# RM-KM-CS.net
KiCad netlist of a schematic drawn in Altium Designer
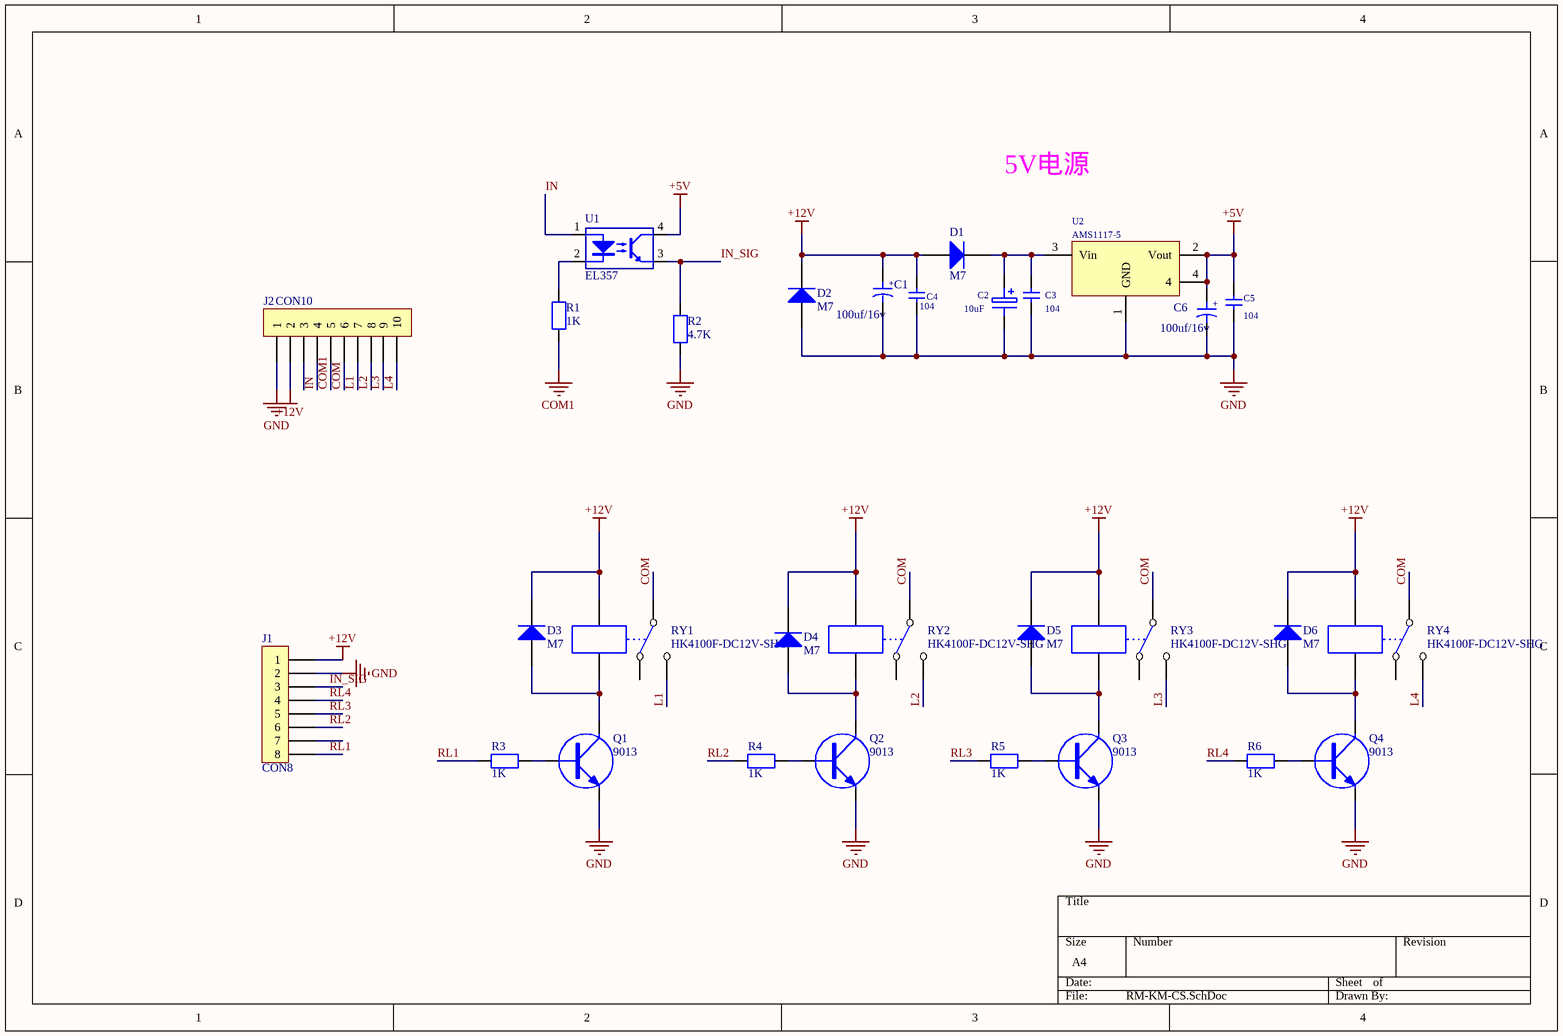
[diagram p0: RM-KM-CS.SchDoc]

(export (version "E")
  (design (tool "Eeschema 10.0.6"))
  (components
    (comp (ref "C1") (value "100uf/16v") (footprint "CAP-DIP4*7") (libsource (lib "gsd") (part "ECAP")))
    (comp (ref "C2")
      (value "10uF")
      (footprint "1206C")
      (description "Electrolytic Capacitor")
      (libsource (lib "*") (part "ELECTRO1"))
    )
    (comp (ref "C3") (value "104") (footprint "0805C") (libsource (lib "*") (part "CAP")))
    (comp (ref "C4") (value "104") (footprint "0805C") (libsource (lib "*") (part "CAP")))
    (comp (ref "C5") (value "104") (footprint "0805C") (libsource (lib "*") (part "CAP")))
    (comp (ref "C6") (value "100uf/16v") (footprint "CAP-DIP4*7") (libsource (lib "gsd") (part "ECAP")))
    (comp (ref "D1") (value "M7") (footprint "M7") (libsource (lib "gsd") (part "M7")))
    (comp (ref "D2") (value "M7") (footprint "M7") (libsource (lib "gsd") (part "M7")))
    (comp (ref "D3") (value "M7") (footprint "M7") (libsource (lib "gsd") (part "M7")))
    (comp (ref "D4") (value "M7") (footprint "M7") (libsource (lib "gsd") (part "M7")))
    (comp (ref "D5") (value "M7") (footprint "M7") (libsource (lib "gsd") (part "M7")))
    (comp (ref "D6") (value "M7") (footprint "M7") (libsource (lib "gsd") (part "M7")))
    (comp (ref "J1") (value "CON8") (footprint "DIP-8P-2.0 -1") (libsource (lib "gsd") (part "CON8")))
    (comp (ref "J2") (value "CON10") (footprint "SPI-10P-5.0_S") (libsource (lib "gsd") (part "CON10")))
    (comp (ref "Q1") (value "9013") (footprint "SOT-23") (libsource (lib "gsd") (part "9013")))
    (comp (ref "Q2") (value "9013") (footprint "SOT-23") (libsource (lib "gsd") (part "9013")))
    (comp (ref "Q3") (value "9013") (footprint "SOT-23") (libsource (lib "gsd") (part "9013")))
    (comp (ref "Q4") (value "9013") (footprint "SOT-23") (libsource (lib "gsd") (part "9013")))
    (comp (ref "R1") (value "1K") (footprint "0805R") (libsource (lib "gsd") (part "RES")))
    (comp (ref "R2") (value "4.7K") (footprint "0805R") (libsource (lib "gsd") (part "RES")))
    (comp (ref "R3") (value "1K") (footprint "0805R") (libsource (lib "") (part "RES_1")))
    (comp (ref "R4") (value "1K") (footprint "0805R") (libsource (lib "") (part "RES_1")))
    (comp (ref "R5") (value "1K") (footprint "0805R") (libsource (lib "") (part "RES_1")))
    (comp (ref "R6") (value "1K") (footprint "0805R") (libsource (lib "") (part "RES_1")))
    (comp (ref "RY1")
      (value "HK4100F-DC12V-SHG")
      (footprint "RELAY")
      (libsource (lib "gsd") (part "RELAY5V"))
    )
    (comp (ref "RY2")
      (value "HK4100F-DC12V-SHG")
      (footprint "RELAY")
      (libsource (lib "gsd") (part "RELAY5V"))
    )
    (comp (ref "RY3")
      (value "HK4100F-DC12V-SHG")
      (footprint "RELAY")
      (libsource (lib "gsd") (part "RELAY5V"))
    )
    (comp (ref "RY4")
      (value "HK4100F-DC12V-SHG")
      (footprint "RELAY")
      (libsource (lib "gsd") (part "RELAY5V"))
    )
    (comp (ref "U1") (value "EL357") (footprint "EL357") (libsource (lib "gsd") (part "817")))
    (comp (ref "U2") (value "AMS1117-5") (footprint "SOT-223") (libsource (lib "*") (part "VOL")))
  )
  (nets
    (net (code "1") (name "+5V") (class "Default")
      (node (ref "C5") (pin "1") (pinfunction "1_1") (pintype "passive"))
      (node (ref "C6") (pin "1") (pinfunction "1_1") (pintype "passive"))
      (node (ref "U1") (pin "4") (pinfunction "Collector_4") (pintype "passive"))
      (node (ref "U2") (pin "2") (pinfunction "Vout_2") (pintype "passive"))
      (node (ref "U2") (pin "4") (pinfunction "4_4") (pintype "passive"))
    )
    (net (code "2") (name "+12V") (class "Default")
      (node (ref "C1") (pin "1") (pinfunction "1_1") (pintype "passive"))
      (node (ref "C4") (pin "1") (pinfunction "1_1") (pintype "passive"))
      (node (ref "D1") (pin "A") (pinfunction "1_A") (pintype "passive"))
      (node (ref "D2") (pin "K") (pinfunction "2_K") (pintype "passive"))
      (node (ref "D3") (pin "K") (pinfunction "2_K") (pintype "passive"))
      (node (ref "D4") (pin "K") (pinfunction "2_K") (pintype "passive"))
      (node (ref "D5") (pin "K") (pinfunction "2_K") (pintype "passive"))
      (node (ref "D6") (pin "K") (pinfunction "2_K") (pintype "passive"))
      (node (ref "J1") (pin "1") (pinfunction "1_1") (pintype "passive"))
      (node (ref "J2") (pin "2") (pinfunction "2_2") (pintype "passive"))
      (node (ref "RY1") (pin "2") (pinfunction "2_2") (pintype "passive"))
      (node (ref "RY2") (pin "2") (pinfunction "2_2") (pintype "passive"))
      (node (ref "RY3") (pin "2") (pinfunction "2_2") (pintype "passive"))
      (node (ref "RY4") (pin "2") (pinfunction "2_2") (pintype "passive"))
    )
    (net (code "3") (name "/COM") (class "Default")
      (node (ref "J2") (pin "6") (pinfunction "6_6") (pintype "passive"))
      (node (ref "RY1") (pin "1") (pinfunction "1_1") (pintype "passive"))
      (node (ref "RY2") (pin "1") (pinfunction "1_1") (pintype "passive"))
      (node (ref "RY3") (pin "1") (pinfunction "1_1") (pintype "passive"))
      (node (ref "RY4") (pin "1") (pinfunction "1_1") (pintype "passive"))
    )
    (net (code "4") (name "/IN") (class "Default")
      (node (ref "J2") (pin "4") (pinfunction "4_4") (pintype "passive"))
      (node (ref "U1") (pin "1") (pinfunction "LED_Anode_1") (pintype "passive"))
    )
    (net (code "5") (name "/IN_SIG") (class "Default")
      (node (ref "J1") (pin "3") (pinfunction "3_3") (pintype "passive"))
      (node (ref "R2") (pin "2") (pinfunction "2_2") (pintype "passive"))
      (node (ref "U1") (pin "3") (pinfunction "Emitter_3") (pintype "passive"))
    )
    (net (code "6") (name "/L1") (class "Default")
      (node (ref "J2") (pin "7") (pinfunction "7_7") (pintype "passive"))
      (node (ref "RY1") (pin "4") (pinfunction "4_4") (pintype "passive"))
    )
    (net (code "7") (name "/L2") (class "Default")
      (node (ref "J2") (pin "8") (pinfunction "8_8") (pintype "passive"))
      (node (ref "RY2") (pin "4") (pinfunction "4_4") (pintype "passive"))
    )
    (net (code "8") (name "/L3") (class "Default")
      (node (ref "J2") (pin "9") (pinfunction "9_9") (pintype "passive"))
      (node (ref "RY3") (pin "4") (pinfunction "4_4") (pintype "passive"))
    )
    (net (code "9") (name "/L4") (class "Default")
      (node (ref "J2") (pin "10") (pinfunction "10_10") (pintype "passive"))
      (node (ref "RY4") (pin "4") (pinfunction "4_4") (pintype "passive"))
    )
    (net (code "10") (name "/RL1") (class "Default")
      (node (ref "J1") (pin "8") (pinfunction "8_8") (pintype "passive"))
      (node (ref "R3") (pin "2") (pinfunction "2_2") (pintype "passive"))
    )
    (net (code "11") (name "/RL2") (class "Default")
      (node (ref "J1") (pin "6") (pinfunction "6_6") (pintype "passive"))
      (node (ref "R4") (pin "2") (pinfunction "2_2") (pintype "passive"))
    )
    (net (code "12") (name "/RL3") (class "Default")
      (node (ref "J1") (pin "5") (pinfunction "5_5") (pintype "passive"))
      (node (ref "R5") (pin "2") (pinfunction "2_2") (pintype "passive"))
    )
    (net (code "13") (name "/RL4") (class "Default")
      (node (ref "J1") (pin "4") (pinfunction "4_4") (pintype "passive"))
      (node (ref "R6") (pin "2") (pinfunction "2_2") (pintype "passive"))
    )
    (net (code "14") (name "COM1") (class "Default")
      (node (ref "J2") (pin "5") (pinfunction "5_5") (pintype "passive"))
      (node (ref "R1") (pin "1") (pinfunction "1_1") (pintype "passive"))
    )
    (net (code "15") (name "GND") (class "Default")
      (node (ref "C1") (pin "2") (pinfunction "2_2") (pintype "passive"))
      (node (ref "C2") (pin "2") (pinfunction "2_2") (pintype "passive"))
      (node (ref "C3") (pin "2") (pinfunction "2_2") (pintype "passive"))
      (node (ref "C4") (pin "2") (pinfunction "2_2") (pintype "passive"))
      (node (ref "C5") (pin "2") (pinfunction "2_2") (pintype "passive"))
      (node (ref "C6") (pin "2") (pinfunction "2_2") (pintype "passive"))
      (node (ref "D2") (pin "A") (pinfunction "1_A") (pintype "passive"))
      (node (ref "J1") (pin "2") (pinfunction "2_2") (pintype "passive"))
      (node (ref "J2") (pin "1") (pinfunction "1_1") (pintype "passive"))
      (node (ref "Q1") (pin "2") (pintype "passive"))
      (node (ref "Q2") (pin "2") (pintype "passive"))
      (node (ref "Q3") (pin "2") (pintype "passive"))
      (node (ref "Q4") (pin "2") (pintype "passive"))
      (node (ref "R2") (pin "1") (pinfunction "1_1") (pintype "passive"))
      (node (ref "U2") (pin "1") (pinfunction "GND_1") (pintype "passive"))
    )
    (net (code "16") (name "Net-(D1-2)") (class "Default")
      (node (ref "C2") (pin "1") (pinfunction "1_1") (pintype "passive"))
      (node (ref "C3") (pin "1") (pinfunction "1_1") (pintype "passive"))
      (node (ref "D1") (pin "K") (pinfunction "2_K") (pintype "passive"))
      (node (ref "U2") (pin "3") (pinfunction "Vin_3") (pintype "passive"))
    )
    (net (code "17") (name "Net-(D3-1)") (class "Default")
      (node (ref "D3") (pin "A") (pinfunction "1_A") (pintype "passive"))
      (node (ref "Q1") (pin "3") (pintype "passive"))
      (node (ref "RY1") (pin "5") (pinfunction "5_5") (pintype "passive"))
    )
    (net (code "18") (name "Net-(D4-1)") (class "Default")
      (node (ref "D4") (pin "A") (pinfunction "1_A") (pintype "passive"))
      (node (ref "Q2") (pin "3") (pintype "passive"))
      (node (ref "RY2") (pin "5") (pinfunction "5_5") (pintype "passive"))
    )
    (net (code "19") (name "Net-(D5-1)") (class "Default")
      (node (ref "D5") (pin "A") (pinfunction "1_A") (pintype "passive"))
      (node (ref "Q3") (pin "3") (pintype "passive"))
      (node (ref "RY3") (pin "5") (pinfunction "5_5") (pintype "passive"))
    )
    (net (code "20") (name "Net-(D6-1)") (class "Default")
      (node (ref "D6") (pin "A") (pinfunction "1_A") (pintype "passive"))
      (node (ref "Q4") (pin "3") (pintype "passive"))
      (node (ref "RY4") (pin "5") (pinfunction "5_5") (pintype "passive"))
    )
    (net (code "21") (name "Net-(Q1-Pad1)") (class "Default")
      (node (ref "Q1") (pin "1") (pintype "passive"))
      (node (ref "R3") (pin "1") (pinfunction "1_1") (pintype "passive"))
    )
    (net (code "22") (name "Net-(Q2-Pad1)") (class "Default")
      (node (ref "Q2") (pin "1") (pintype "passive"))
      (node (ref "R4") (pin "1") (pinfunction "1_1") (pintype "passive"))
    )
    (net (code "23") (name "Net-(Q3-Pad1)") (class "Default")
      (node (ref "Q3") (pin "1") (pintype "passive"))
      (node (ref "R5") (pin "1") (pinfunction "1_1") (pintype "passive"))
    )
    (net (code "24") (name "Net-(Q4-Pad1)") (class "Default")
      (node (ref "Q4") (pin "1") (pintype "passive"))
      (node (ref "R6") (pin "1") (pinfunction "1_1") (pintype "passive"))
    )
    (net (code "25") (name "Net-(U1-LED_Cathode)") (class "Default")
      (node (ref "R1") (pin "2") (pinfunction "2_2") (pintype "passive"))
      (node (ref "U1") (pin "2") (pinfunction "LED_Cathode_2") (pintype "passive"))
    )
    (net (code "26") (name "unconnected-(J1-Pad7)") (class "Default")
      (node (ref "J1") (pin "7") (pinfunction "7_7") (pintype "passive"))
    )
    (net (code "27") (name "unconnected-(J2-Pad3)") (class "Default")
      (node (ref "J2") (pin "3") (pinfunction "3_3") (pintype "passive"))
    )
    (net (code "28") (name "unconnected-(RY1-Pad3)") (class "Default")
      (node (ref "RY1") (pin "3") (pinfunction "3_3") (pintype "passive"))
    )
    (net (code "29") (name "unconnected-(RY2-Pad3)") (class "Default")
      (node (ref "RY2") (pin "3") (pinfunction "3_3") (pintype "passive"))
    )
    (net (code "30") (name "unconnected-(RY3-Pad3)") (class "Default")
      (node (ref "RY3") (pin "3") (pinfunction "3_3") (pintype "passive"))
    )
    (net (code "31") (name "unconnected-(RY4-Pad3)") (class "Default")
      (node (ref "RY4") (pin "3") (pinfunction "3_3") (pintype "passive"))
    )
  )
)
